# 505153_1_2.net
KiCad netlist of a schematic drawn in Altium Designer
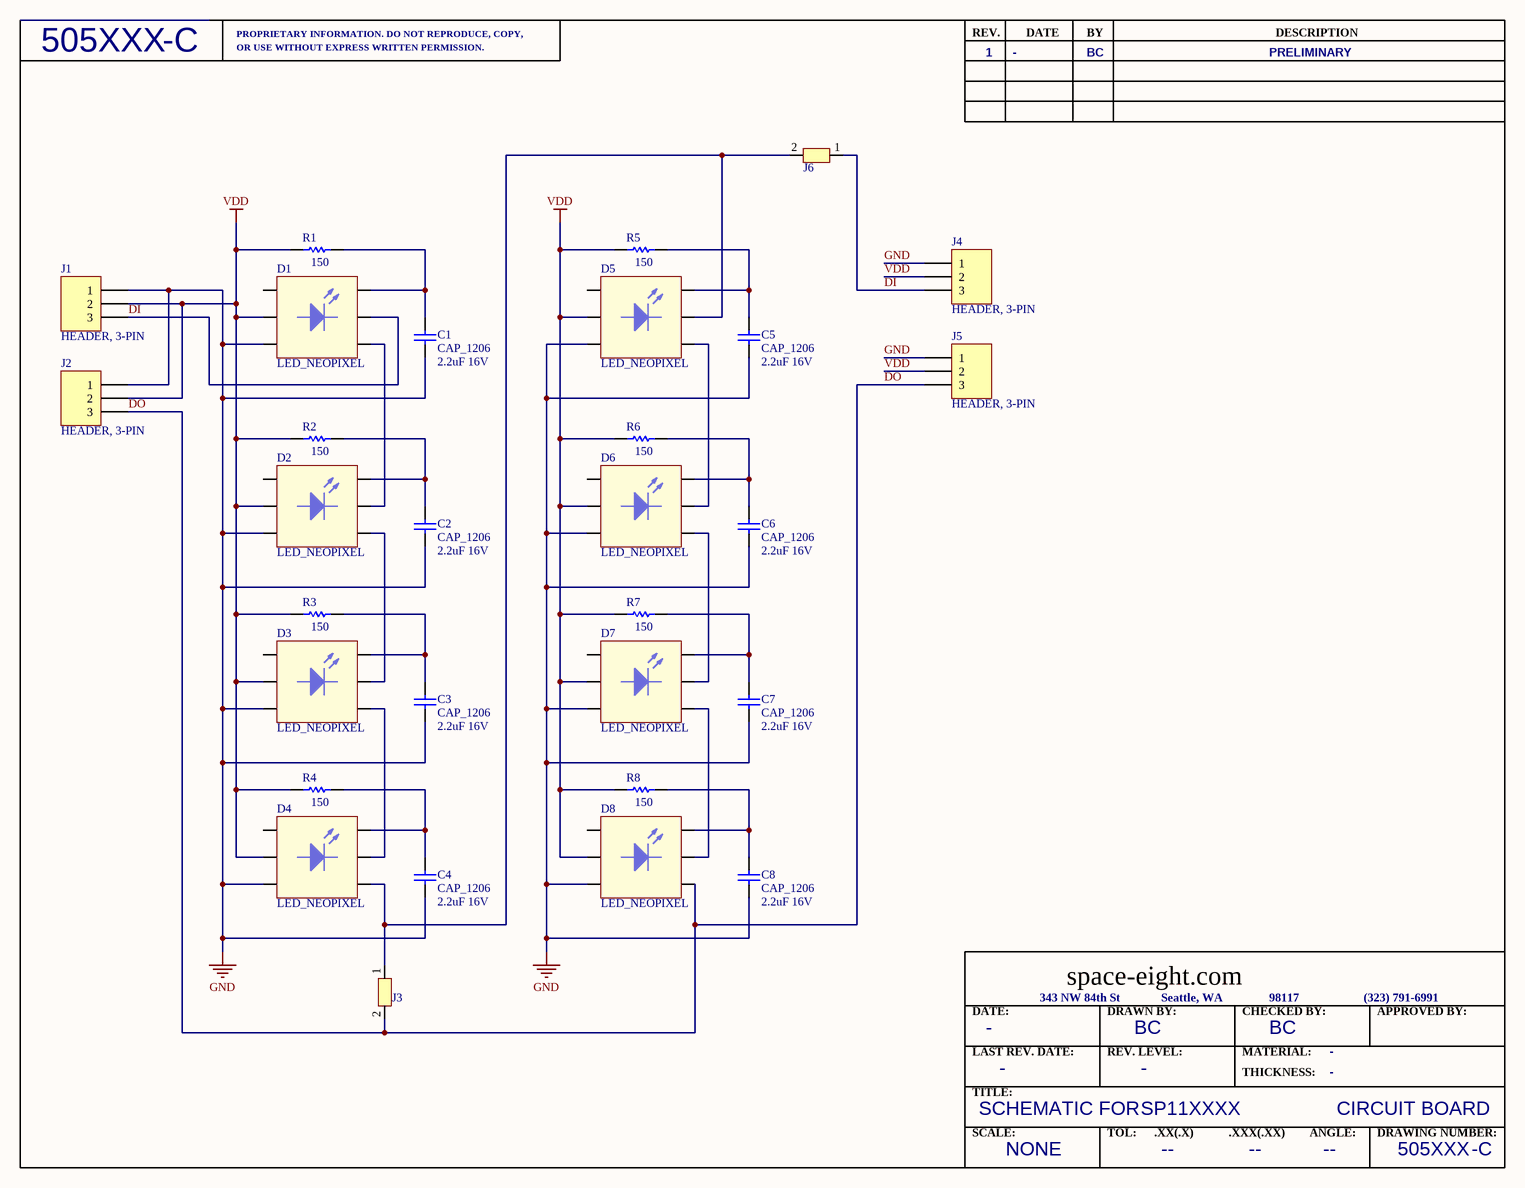
[diagram p0: 505153_1_2.SchDoc]

(export (version "E")
  (design (tool "Eeschema 10.0.6"))
  (components
    (comp (ref "C1")
      (value "CAP_1206")
      (footprint "SMT_1206_MOD")
      (description "CAP")
      (fields
        (field (name "MANUFACTURER") "Generic Components")
        (field (name "ALTIUM_VALUE") "2.2uF 16V")
        (field (name "PUBLISHER") "Altium Limited")
      )
      (libsource (lib "Custom_Lib_2") (part "CAP_1206"))
    )
    (comp (ref "C2")
      (value "CAP_1206")
      (footprint "SMT_1206_MOD")
      (description "CAP")
      (fields
        (field (name "MANUFACTURER") "Generic Components")
        (field (name "ALTIUM_VALUE") "2.2uF 16V")
        (field (name "PUBLISHER") "Altium Limited")
      )
      (libsource (lib "Custom_Lib_2") (part "CAP_1206"))
    )
    (comp (ref "C3")
      (value "CAP_1206")
      (footprint "SMT_1206_MOD")
      (description "CAP")
      (fields
        (field (name "MANUFACTURER") "Generic Components")
        (field (name "ALTIUM_VALUE") "2.2uF 16V")
        (field (name "PUBLISHER") "Altium Limited")
      )
      (libsource (lib "Custom_Lib_2") (part "CAP_1206"))
    )
    (comp (ref "C4")
      (value "CAP_1206")
      (footprint "SMT_1206_MOD")
      (description "CAP")
      (fields
        (field (name "MANUFACTURER") "Generic Components")
        (field (name "ALTIUM_VALUE") "2.2uF 16V")
        (field (name "PUBLISHER") "Altium Limited")
      )
      (libsource (lib "Custom_Lib_2") (part "CAP_1206"))
    )
    (comp (ref "C5")
      (value "CAP_1206")
      (footprint "SMT_1206_MOD")
      (description "CAP")
      (fields
        (field (name "MANUFACTURER") "Generic Components")
        (field (name "ALTIUM_VALUE") "2.2uF 16V")
        (field (name "PUBLISHER") "Altium Limited")
      )
      (libsource (lib "Custom_Lib_2") (part "CAP_1206"))
    )
    (comp (ref "C6")
      (value "CAP_1206")
      (footprint "SMT_1206_MOD")
      (description "CAP")
      (fields
        (field (name "MANUFACTURER") "Generic Components")
        (field (name "ALTIUM_VALUE") "2.2uF 16V")
        (field (name "PUBLISHER") "Altium Limited")
      )
      (libsource (lib "Custom_Lib_2") (part "CAP_1206"))
    )
    (comp (ref "C7")
      (value "CAP_1206")
      (footprint "SMT_1206_MOD")
      (description "CAP")
      (fields
        (field (name "MANUFACTURER") "Generic Components")
        (field (name "ALTIUM_VALUE") "2.2uF 16V")
        (field (name "PUBLISHER") "Altium Limited")
      )
      (libsource (lib "Custom_Lib_2") (part "CAP_1206"))
    )
    (comp (ref "C8")
      (value "CAP_1206")
      (footprint "SMT_1206_MOD")
      (description "CAP")
      (fields
        (field (name "MANUFACTURER") "Generic Components")
        (field (name "ALTIUM_VALUE") "2.2uF 16V")
        (field (name "PUBLISHER") "Altium Limited")
      )
      (libsource (lib "Custom_Lib_2") (part "CAP_1206"))
    )
    (comp (ref "D1")
      (value "LED_NEOPIXEL")
      (footprint "NEOPIXEL")
      (description "RGB NEOPIXEL")
      (fields (field (name "MANUFACTURER") "Generic Components") (field (name "PUBLISHER") "Altium Limited"))
      (libsource (lib "Custom_Lib_2") (part "LED_NEOPIXEL"))
    )
    (comp (ref "D2")
      (value "LED_NEOPIXEL")
      (footprint "NEOPIXEL")
      (description "RGB NEOPIXEL")
      (fields (field (name "MANUFACTURER") "Generic Components") (field (name "PUBLISHER") "Altium Limited"))
      (libsource (lib "Custom_Lib_2") (part "LED_NEOPIXEL"))
    )
    (comp (ref "D3")
      (value "LED_NEOPIXEL")
      (footprint "NEOPIXEL")
      (description "RGB NEOPIXEL")
      (fields (field (name "MANUFACTURER") "Generic Components") (field (name "PUBLISHER") "Altium Limited"))
      (libsource (lib "Custom_Lib_2") (part "LED_NEOPIXEL"))
    )
    (comp (ref "D4")
      (value "LED_NEOPIXEL")
      (footprint "NEOPIXEL")
      (description "RGB NEOPIXEL")
      (fields (field (name "MANUFACTURER") "Generic Components") (field (name "PUBLISHER") "Altium Limited"))
      (libsource (lib "Custom_Lib_2") (part "LED_NEOPIXEL"))
    )
    (comp (ref "D5")
      (value "LED_NEOPIXEL")
      (footprint "NEOPIXEL")
      (description "RGB NEOPIXEL")
      (fields (field (name "MANUFACTURER") "Generic Components") (field (name "PUBLISHER") "Altium Limited"))
      (libsource (lib "Custom_Lib_2") (part "LED_NEOPIXEL"))
    )
    (comp (ref "D6")
      (value "LED_NEOPIXEL")
      (footprint "NEOPIXEL")
      (description "RGB NEOPIXEL")
      (fields (field (name "MANUFACTURER") "Generic Components") (field (name "PUBLISHER") "Altium Limited"))
      (libsource (lib "Custom_Lib_2") (part "LED_NEOPIXEL"))
    )
    (comp (ref "D7")
      (value "LED_NEOPIXEL")
      (footprint "NEOPIXEL")
      (description "RGB NEOPIXEL")
      (fields (field (name "MANUFACTURER") "Generic Components") (field (name "PUBLISHER") "Altium Limited"))
      (libsource (lib "Custom_Lib_2") (part "LED_NEOPIXEL"))
    )
    (comp (ref "D8")
      (value "LED_NEOPIXEL")
      (footprint "NEOPIXEL")
      (description "RGB NEOPIXEL")
      (fields (field (name "MANUFACTURER") "Generic Components") (field (name "PUBLISHER") "Altium Limited"))
      (libsource (lib "Custom_Lib_2") (part "LED_NEOPIXEL"))
    )
    (comp (ref "J1")
      (value "HEADER, 3-PIN")
      (footprint "HEADER, 3-pin")
      (description "Header, 3-Pin")
      (fields (field (name "PUBLISHER") "Altium Limited"))
      (libsource (lib "Custom_Lib_2") (part "HEADER, 3-PIN_1"))
    )
    (comp (ref "J2")
      (value "HEADER, 3-PIN")
      (footprint "HEADER, 3-pin")
      (description "Header, 3-Pin")
      (fields (field (name "PUBLISHER") "Altium Limited"))
      (libsource (lib "Custom_Lib_2") (part "HEADER, 3-PIN_1"))
    )
    (comp (ref "J3") (value "JUMPER_MOD") (footprint "JUMPER_SMT") (libsource (lib "") (part "JUMPER_MOD_1")))
    (comp (ref "J4")
      (value "HEADER, 3-PIN")
      (footprint "HEADER, 3-pin")
      (description "Header, 3-Pin")
      (fields (field (name "PUBLISHER") "Altium Limited"))
      (libsource (lib "") (part "HEADER, 3-PIN_1_1"))
    )
    (comp (ref "J5")
      (value "HEADER, 3-PIN")
      (footprint "HEADER, 3-pin")
      (description "Header, 3-Pin")
      (fields (field (name "PUBLISHER") "Altium Limited"))
      (libsource (lib "") (part "HEADER, 3-PIN_1_1"))
    )
    (comp (ref "J6")
      (value "JUMPER_MOD")
      (footprint "JUMPER_SMT")
      (libsource (lib "Custom_Lib_2") (part "JUMPER_MOD"))
    )
    (comp (ref "R1")
      (value "150")
      (footprint "SMT_1206_MOD")
      (description "RES")
      (fields
        (field (name "MANUFACTURER") "Generic Components")
        (field (name "Comment") "RES_1206")
        (field (name "PUBLISHER") "Altium Limited")
      )
      (libsource (lib "Custom_Lib_2") (part "RES_1206"))
    )
    (comp (ref "R2")
      (value "150")
      (footprint "SMT_1206_MOD")
      (description "RES")
      (fields
        (field (name "MANUFACTURER") "Generic Components")
        (field (name "Comment") "RES_1206")
        (field (name "PUBLISHER") "Altium Limited")
      )
      (libsource (lib "Custom_Lib_2") (part "RES_1206"))
    )
    (comp (ref "R3")
      (value "150")
      (footprint "SMT_1206_MOD")
      (description "RES")
      (fields
        (field (name "MANUFACTURER") "Generic Components")
        (field (name "Comment") "RES_1206")
        (field (name "PUBLISHER") "Altium Limited")
      )
      (libsource (lib "Custom_Lib_2") (part "RES_1206"))
    )
    (comp (ref "R4")
      (value "150")
      (footprint "SMT_1206_MOD")
      (description "RES")
      (fields
        (field (name "MANUFACTURER") "Generic Components")
        (field (name "Comment") "RES_1206")
        (field (name "PUBLISHER") "Altium Limited")
      )
      (libsource (lib "Custom_Lib_2") (part "RES_1206"))
    )
    (comp (ref "R5")
      (value "150")
      (footprint "SMT_1206_MOD")
      (description "RES")
      (fields
        (field (name "MANUFACTURER") "Generic Components")
        (field (name "Comment") "RES_1206")
        (field (name "PUBLISHER") "Altium Limited")
      )
      (libsource (lib "Custom_Lib_2") (part "RES_1206"))
    )
    (comp (ref "R6")
      (value "150")
      (footprint "SMT_1206_MOD")
      (description "RES")
      (fields
        (field (name "MANUFACTURER") "Generic Components")
        (field (name "Comment") "RES_1206")
        (field (name "PUBLISHER") "Altium Limited")
      )
      (libsource (lib "Custom_Lib_2") (part "RES_1206"))
    )
    (comp (ref "R7")
      (value "150")
      (footprint "SMT_1206_MOD")
      (description "RES")
      (fields
        (field (name "MANUFACTURER") "Generic Components")
        (field (name "Comment") "RES_1206")
        (field (name "PUBLISHER") "Altium Limited")
      )
      (libsource (lib "Custom_Lib_2") (part "RES_1206"))
    )
    (comp (ref "R8")
      (value "150")
      (footprint "SMT_1206_MOD")
      (description "RES")
      (fields
        (field (name "MANUFACTURER") "Generic Components")
        (field (name "Comment") "RES_1206")
        (field (name "PUBLISHER") "Altium Limited")
      )
      (libsource (lib "Custom_Lib_2") (part "RES_1206"))
    )
  )
  (nets
    (net (code "1") (name "/DI") (class "Default")
      (node (ref "D1") (pin "2") (pinfunction "DI_2") (pintype "passive"))
      (node (ref "J1") (pin "3") (pinfunction "3_3") (pintype "passive"))
      (node (ref "J4") (pin "3") (pinfunction "3_3") (pintype "passive"))
      (node (ref "J6") (pin "1") (pinfunction "I/_1") (pintype "passive"))
    )
    (net (code "2") (name "/DO") (class "Default")
      (node (ref "D8") (pin "1") (pinfunction "DO_1") (pintype "passive"))
      (node (ref "J2") (pin "3") (pinfunction "3_3") (pintype "passive"))
      (node (ref "J3") (pin "2") (pinfunction "O_2") (pintype "passive"))
      (node (ref "J5") (pin "3") (pinfunction "3_3") (pintype "passive"))
    )
    (net (code "3") (name "GND") (class "Default")
      (node (ref "C1") (pin "1") (pinfunction "1_1") (pintype "passive"))
      (node (ref "C2") (pin "1") (pinfunction "1_1") (pintype "passive"))
      (node (ref "C3") (pin "1") (pinfunction "1_1") (pintype "passive"))
      (node (ref "C4") (pin "1") (pinfunction "1_1") (pintype "passive"))
      (node (ref "C5") (pin "1") (pinfunction "1_1") (pintype "passive"))
      (node (ref "C6") (pin "1") (pinfunction "1_1") (pintype "passive"))
      (node (ref "C7") (pin "1") (pinfunction "1_1") (pintype "passive"))
      (node (ref "C8") (pin "1") (pinfunction "1_1") (pintype "passive"))
      (node (ref "D1") (pin "6") (pinfunction "VSS_6") (pintype "passive"))
      (node (ref "D2") (pin "6") (pinfunction "VSS_6") (pintype "passive"))
      (node (ref "D3") (pin "6") (pinfunction "VSS_6") (pintype "passive"))
      (node (ref "D4") (pin "6") (pinfunction "VSS_6") (pintype "passive"))
      (node (ref "D5") (pin "6") (pinfunction "VSS_6") (pintype "passive"))
      (node (ref "D6") (pin "6") (pinfunction "VSS_6") (pintype "passive"))
      (node (ref "D7") (pin "6") (pinfunction "VSS_6") (pintype "passive"))
      (node (ref "D8") (pin "6") (pinfunction "VSS_6") (pintype "passive"))
      (node (ref "J1") (pin "1") (pinfunction "1_1") (pintype "passive"))
      (node (ref "J2") (pin "1") (pinfunction "1_1") (pintype "passive"))
      (node (ref "J4") (pin "1") (pinfunction "1_1") (pintype "passive"))
      (node (ref "J5") (pin "1") (pinfunction "1_1") (pintype "passive"))
    )
    (net (code "4") (name "Net-(D1-DO)") (class "Default")
      (node (ref "D1") (pin "1") (pinfunction "DO_1") (pintype "passive"))
      (node (ref "D2") (pin "2") (pinfunction "DI_2") (pintype "passive"))
    )
    (net (code "5") (name "Net-(D1-VCC)") (class "Default")
      (node (ref "C1") (pin "2") (pinfunction "2_2") (pintype "passive"))
      (node (ref "D1") (pin "3") (pinfunction "VCC_3") (pintype "passive"))
      (node (ref "R1") (pin "2") (pinfunction "2_2") (pintype "passive"))
    )
    (net (code "6") (name "Net-(D2-DO)") (class "Default")
      (node (ref "D2") (pin "1") (pinfunction "DO_1") (pintype "passive"))
      (node (ref "D3") (pin "2") (pinfunction "DI_2") (pintype "passive"))
    )
    (net (code "7") (name "Net-(D2-VCC)") (class "Default")
      (node (ref "C2") (pin "2") (pinfunction "2_2") (pintype "passive"))
      (node (ref "D2") (pin "3") (pinfunction "VCC_3") (pintype "passive"))
      (node (ref "R2") (pin "2") (pinfunction "2_2") (pintype "passive"))
    )
    (net (code "8") (name "Net-(D3-DO)") (class "Default")
      (node (ref "D3") (pin "1") (pinfunction "DO_1") (pintype "passive"))
      (node (ref "D4") (pin "2") (pinfunction "DI_2") (pintype "passive"))
    )
    (net (code "9") (name "Net-(D3-VCC)") (class "Default")
      (node (ref "C3") (pin "2") (pinfunction "2_2") (pintype "passive"))
      (node (ref "D3") (pin "3") (pinfunction "VCC_3") (pintype "passive"))
      (node (ref "R3") (pin "2") (pinfunction "2_2") (pintype "passive"))
    )
    (net (code "10") (name "Net-(D4-DO)") (class "Default")
      (node (ref "D4") (pin "1") (pinfunction "DO_1") (pintype "passive"))
      (node (ref "D5") (pin "2") (pinfunction "DI_2") (pintype "passive"))
      (node (ref "J3") (pin "1") (pinfunction "I/_1") (pintype "passive"))
      (node (ref "J6") (pin "2") (pinfunction "O_2") (pintype "passive"))
    )
    (net (code "11") (name "Net-(D4-VCC)") (class "Default")
      (node (ref "C4") (pin "2") (pinfunction "2_2") (pintype "passive"))
      (node (ref "D4") (pin "3") (pinfunction "VCC_3") (pintype "passive"))
      (node (ref "R4") (pin "2") (pinfunction "2_2") (pintype "passive"))
    )
    (net (code "12") (name "Net-(D5-DO)") (class "Default")
      (node (ref "D5") (pin "1") (pinfunction "DO_1") (pintype "passive"))
      (node (ref "D6") (pin "2") (pinfunction "DI_2") (pintype "passive"))
    )
    (net (code "13") (name "Net-(D5-VCC)") (class "Default")
      (node (ref "C5") (pin "2") (pinfunction "2_2") (pintype "passive"))
      (node (ref "D5") (pin "3") (pinfunction "VCC_3") (pintype "passive"))
      (node (ref "R5") (pin "2") (pinfunction "2_2") (pintype "passive"))
    )
    (net (code "14") (name "Net-(D6-DO)") (class "Default")
      (node (ref "D6") (pin "1") (pinfunction "DO_1") (pintype "passive"))
      (node (ref "D7") (pin "2") (pinfunction "DI_2") (pintype "passive"))
    )
    (net (code "15") (name "Net-(D6-VCC)") (class "Default")
      (node (ref "C6") (pin "2") (pinfunction "2_2") (pintype "passive"))
      (node (ref "D6") (pin "3") (pinfunction "VCC_3") (pintype "passive"))
      (node (ref "R6") (pin "2") (pinfunction "2_2") (pintype "passive"))
    )
    (net (code "16") (name "Net-(D7-DO)") (class "Default")
      (node (ref "D7") (pin "1") (pinfunction "DO_1") (pintype "passive"))
      (node (ref "D8") (pin "2") (pinfunction "DI_2") (pintype "passive"))
    )
    (net (code "17") (name "Net-(D7-VCC)") (class "Default")
      (node (ref "C7") (pin "2") (pinfunction "2_2") (pintype "passive"))
      (node (ref "D7") (pin "3") (pinfunction "VCC_3") (pintype "passive"))
      (node (ref "R7") (pin "2") (pinfunction "2_2") (pintype "passive"))
    )
    (net (code "18") (name "Net-(D8-VCC)") (class "Default")
      (node (ref "C8") (pin "2") (pinfunction "2_2") (pintype "passive"))
      (node (ref "D8") (pin "3") (pinfunction "VCC_3") (pintype "passive"))
      (node (ref "R8") (pin "2") (pinfunction "2_2") (pintype "passive"))
    )
    (net (code "19") (name "VDD") (class "Default")
      (node (ref "D1") (pin "5") (pinfunction "VDD_5") (pintype "passive"))
      (node (ref "D2") (pin "5") (pinfunction "VDD_5") (pintype "passive"))
      (node (ref "D3") (pin "5") (pinfunction "VDD_5") (pintype "passive"))
      (node (ref "D4") (pin "5") (pinfunction "VDD_5") (pintype "passive"))
      (node (ref "D5") (pin "5") (pinfunction "VDD_5") (pintype "passive"))
      (node (ref "D6") (pin "5") (pinfunction "VDD_5") (pintype "passive"))
      (node (ref "D7") (pin "5") (pinfunction "VDD_5") (pintype "passive"))
      (node (ref "D8") (pin "5") (pinfunction "VDD_5") (pintype "passive"))
      (node (ref "J1") (pin "2") (pinfunction "2_2") (pintype "passive"))
      (node (ref "J2") (pin "2") (pinfunction "2_2") (pintype "passive"))
      (node (ref "J4") (pin "2") (pinfunction "2_2") (pintype "passive"))
      (node (ref "J5") (pin "2") (pinfunction "2_2") (pintype "passive"))
      (node (ref "R1") (pin "1") (pinfunction "1_1") (pintype "passive"))
      (node (ref "R2") (pin "1") (pinfunction "1_1") (pintype "passive"))
      (node (ref "R3") (pin "1") (pinfunction "1_1") (pintype "passive"))
      (node (ref "R4") (pin "1") (pinfunction "1_1") (pintype "passive"))
      (node (ref "R5") (pin "1") (pinfunction "1_1") (pintype "passive"))
      (node (ref "R6") (pin "1") (pinfunction "1_1") (pintype "passive"))
      (node (ref "R7") (pin "1") (pinfunction "1_1") (pintype "passive"))
      (node (ref "R8") (pin "1") (pinfunction "1_1") (pintype "passive"))
    )
    (net (code "20") (name "unconnected-(D1-NC-Pad4)") (class "Default")
      (node (ref "D1") (pin "4") (pinfunction "NC_4") (pintype "passive"))
    )
    (net (code "21") (name "unconnected-(D2-NC-Pad4)") (class "Default")
      (node (ref "D2") (pin "4") (pinfunction "NC_4") (pintype "passive"))
    )
    (net (code "22") (name "unconnected-(D3-NC-Pad4)") (class "Default")
      (node (ref "D3") (pin "4") (pinfunction "NC_4") (pintype "passive"))
    )
    (net (code "23") (name "unconnected-(D4-NC-Pad4)") (class "Default")
      (node (ref "D4") (pin "4") (pinfunction "NC_4") (pintype "passive"))
    )
    (net (code "24") (name "unconnected-(D5-NC-Pad4)") (class "Default")
      (node (ref "D5") (pin "4") (pinfunction "NC_4") (pintype "passive"))
    )
    (net (code "25") (name "unconnected-(D6-NC-Pad4)") (class "Default")
      (node (ref "D6") (pin "4") (pinfunction "NC_4") (pintype "passive"))
    )
    (net (code "26") (name "unconnected-(D7-NC-Pad4)") (class "Default")
      (node (ref "D7") (pin "4") (pinfunction "NC_4") (pintype "passive"))
    )
    (net (code "27") (name "unconnected-(D8-NC-Pad4)") (class "Default")
      (node (ref "D8") (pin "4") (pinfunction "NC_4") (pintype "passive"))
    )
  )
)
